# Communication_Ethernet_DP.net
KiCad netlist of a schematic drawn in Altium Designer
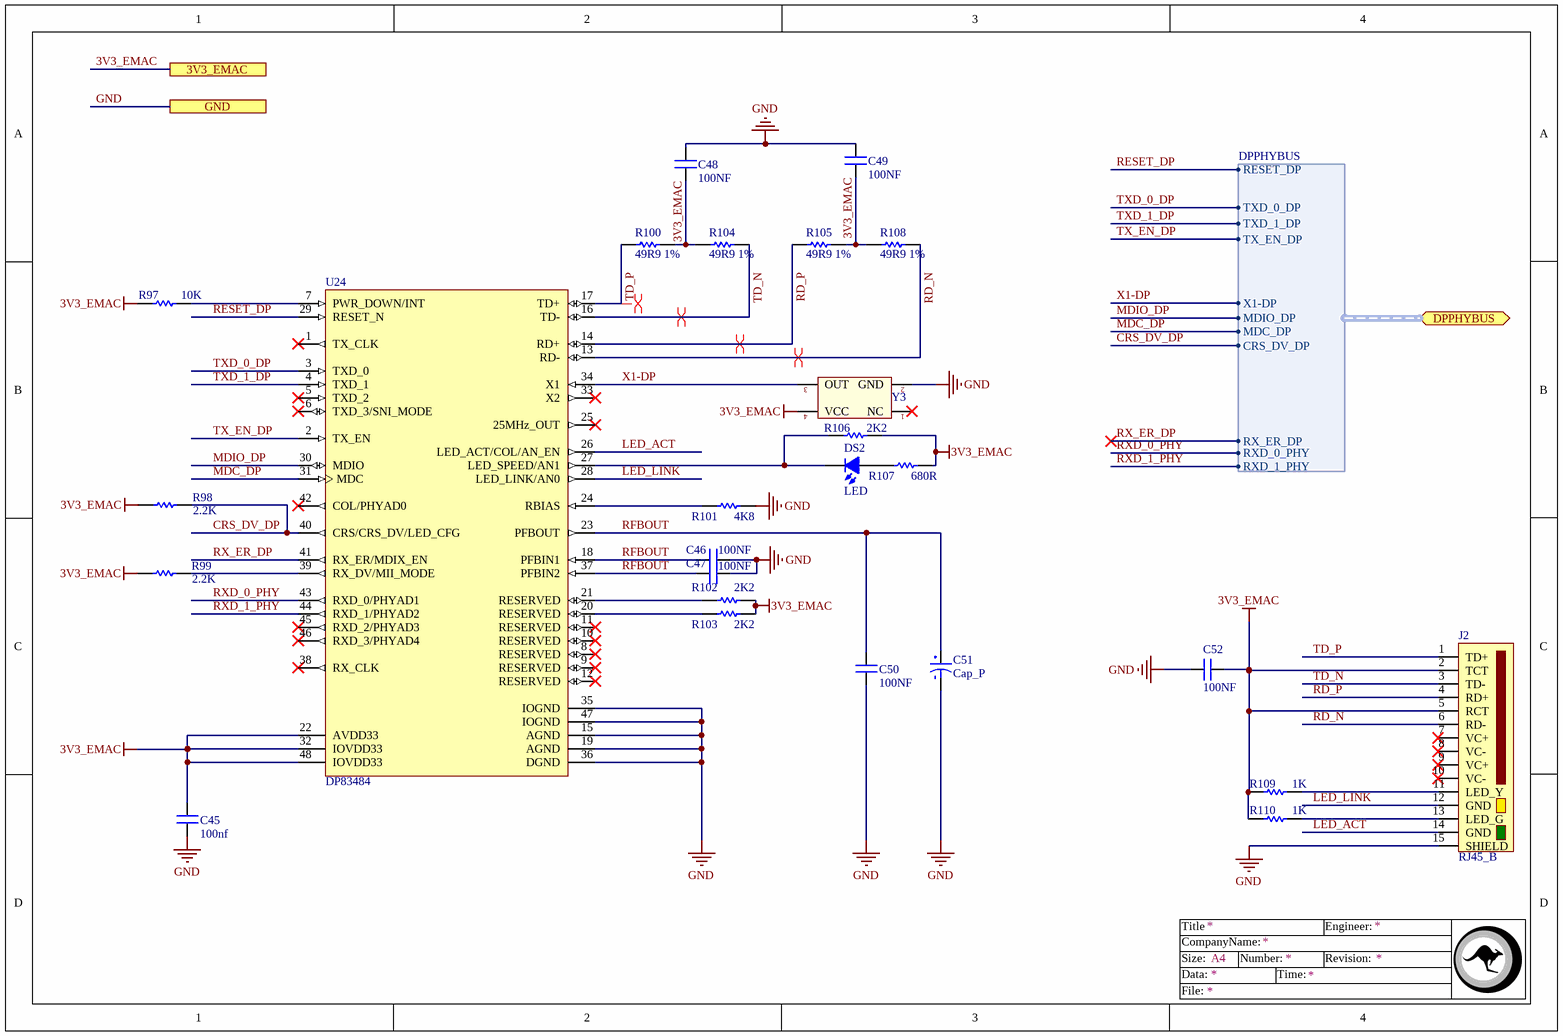
[diagram p0: Communication Ethernet DP.SchDoc]

(export (version "E")
  (design (tool "Eeschema 10.0.6"))
  (components
    (comp (ref "C45")
      (value "100nf")
      (footprint "Cap0805")
      (description "Surface mount Capacitor")
      (libsource (lib "PMLIB2020") (part "Cap"))
    )
    (comp (ref "C46")
      (value "100NF")
      (footprint "Cap0805")
      (description "Surface mount Capacitor")
      (libsource (lib "PMLIB2020") (part "Cap"))
    )
    (comp (ref "C47")
      (value "100NF")
      (footprint "Cap0805")
      (description "Surface mount Capacitor")
      (libsource (lib "PMLIB2020") (part "Cap"))
    )
    (comp (ref "C48")
      (value "100NF")
      (footprint "Cap0805")
      (description "Surface mount Capacitor")
      (libsource (lib "PMLIB2020") (part "Cap"))
    )
    (comp (ref "C49")
      (value "100NF")
      (footprint "Cap0805")
      (description "Surface mount Capacitor")
      (libsource (lib "PMLIB2020") (part "Cap"))
    )
    (comp (ref "C50")
      (value "100NF")
      (footprint "Cap0805")
      (description "Surface mount Capacitor")
      (libsource (lib "PMLIB2020") (part "Cap"))
    )
    (comp (ref "C51")
      (value "Cap_P")
      (footprint "Cap_4mm")
      (description "Polarity")
      (libsource (lib "PMLIB2020") (part "Cap_P"))
    )
    (comp (ref "C52")
      (value "100NF")
      (footprint "Cap0805")
      (description "Surface mount Capacitor")
      (libsource (lib "PMLIB2020") (part "Cap"))
    )
    (comp (ref "DS2") (value "LED") (footprint "Led0805") (libsource (lib "PMLIB2020") (part "LED")))
    (comp (ref "J2")
      (value "RJ45_B")
      (footprint "RJ45_B")
      (description "Ethernet Connector")
      (libsource (lib "PMLIB2020") (part "RJ45_B"))
    )
    (comp (ref "R97")
      (value "10K")
      (footprint "R0805")
      (description "Resistor")
      (libsource (lib "PMLIB2020") (part "Resistor"))
    )
    (comp (ref "R98")
      (value "2.2K")
      (footprint "R0805")
      (description "Resistor")
      (libsource (lib "PMLIB2020") (part "Resistor"))
    )
    (comp (ref "R99")
      (value "2.2K")
      (footprint "R0805")
      (description "Resistor")
      (libsource (lib "PMLIB2020") (part "Resistor"))
    )
    (comp (ref "R100")
      (value "49R9 1%")
      (footprint "R0805")
      (description "Resistor")
      (libsource (lib "PMLIB2020") (part "Resistor"))
    )
    (comp (ref "R101")
      (value "4K8")
      (footprint "R0805")
      (description "Resistor")
      (libsource (lib "PMLIB2020") (part "Resistor"))
    )
    (comp (ref "R102")
      (value "2K2")
      (footprint "R0805")
      (description "Resistor")
      (libsource (lib "PMLIB2020") (part "Resistor"))
    )
    (comp (ref "R103")
      (value "2K2")
      (footprint "R0805")
      (description "Resistor")
      (libsource (lib "PMLIB2020") (part "Resistor"))
    )
    (comp (ref "R104")
      (value "49R9 1%")
      (footprint "R0805")
      (description "Resistor")
      (libsource (lib "PMLIB2020") (part "Resistor"))
    )
    (comp (ref "R105")
      (value "49R9 1%")
      (footprint "R0805")
      (description "Resistor")
      (libsource (lib "PMLIB2020") (part "Resistor"))
    )
    (comp (ref "R106")
      (value "2K2")
      (footprint "R0805")
      (description "Resistor")
      (libsource (lib "PMLIB2020") (part "Resistor"))
    )
    (comp (ref "R107")
      (value "680R")
      (footprint "R0805")
      (description "Resistor")
      (libsource (lib "PMLIB2020") (part "Resistor"))
    )
    (comp (ref "R108")
      (value "49R9 1%")
      (footprint "R0805")
      (description "Resistor")
      (libsource (lib "PMLIB2020") (part "Resistor"))
    )
    (comp (ref "R109")
      (value "1K")
      (footprint "R0805")
      (description "Resistor")
      (libsource (lib "PMLIB2020") (part "Resistor"))
    )
    (comp (ref "R110")
      (value "1K")
      (footprint "R0805")
      (description "Resistor")
      (libsource (lib "PMLIB2020") (part "Resistor"))
    )
    (comp (ref "U24")
      (value "DP83484")
      (footprint "DP83484")
      (description "Ethernet PHY")
      (libsource (lib "PMLIB2020") (part "DP83484"))
    )
    (comp (ref "Y3")
      (value "Oscillator")
      (footprint "Crystall 50Mhz")
      (libsource (lib "PMLIB2020") (part "Oscillator"))
    )
  )
  (nets
    (net (code "2") (name "/CRS_DV_DP") (class "Default")
      (node (ref "R98") (pin "1") (pinfunction "1_1") (pintype "passive"))
      (node (ref "U24") (pin "40") (pinfunction "CRS/CRS_DV/LED_CFG_40") (pintype "output"))
    )
    (net (code "3") (name "/LED_ACT") (class "Default")
      (node (ref "J2") (pin "14") (pinfunction "GND_14") (pintype "passive"))
      (node (ref "U24") (pin "26") (pinfunction "LED_ACT/COL/AN_EN_26") (pintype "output"))
    )
    (net (code "4") (name "/LED_LINK") (class "Default")
      (node (ref "J2") (pin "12") (pinfunction "GND_12") (pintype "passive"))
      (node (ref "U24") (pin "28") (pinfunction "LED_LINK/AN0_28") (pintype "output"))
    )
    (net (code "5") (name "/MDC_DP") (class "Default")
      (node (ref "U24") (pin "31") (pinfunction "MDC_31") (pintype "input"))
    )
    (net (code "6") (name "/MDIO_DP") (class "Default")
      (node (ref "U24") (pin "30") (pinfunction "MDIO_30") (pintype "bidirectional"))
    )
    (net (code "7") (name "/RD_N") (class "Default")
      (node (ref "J2") (pin "6") (pinfunction "RD-_6") (pintype "passive"))
      (node (ref "R108") (pin "2") (pinfunction "2_2") (pintype "passive"))
      (node (ref "U24") (pin "13") (pinfunction "RD-_13") (pintype "bidirectional"))
    )
    (net (code "8") (name "/RD_P") (class "Default")
      (node (ref "J2") (pin "4") (pinfunction "RD+_4") (pintype "passive"))
      (node (ref "R105") (pin "1") (pinfunction "1_1") (pintype "passive"))
      (node (ref "U24") (pin "14") (pinfunction "RD+_14") (pintype "bidirectional"))
    )
    (net (code "9") (name "/RESET_DP") (class "Default")
      (node (ref "U24") (pin "29") (pinfunction "RESET_N_29") (pintype "input"))
    )
    (net (code "10") (name "/RFBOUT") (class "Default")
      (node (ref "C46") (pin "1") (pinfunction "1_1") (pintype "passive"))
      (node (ref "C47") (pin "1") (pinfunction "1_1") (pintype "passive"))
      (node (ref "C50") (pin "2") (pinfunction "2_2") (pintype "passive"))
      (node (ref "C51") (pin "2") (pinfunction "2_2") (pintype "passive"))
      (node (ref "U24") (pin "18") (pinfunction "PFBIN1_18") (pintype "input"))
      (node (ref "U24") (pin "23") (pinfunction "PFBOUT_23") (pintype "output"))
      (node (ref "U24") (pin "37") (pinfunction "PFBIN2_37") (pintype "input"))
    )
    (net (code "11") (name "/RXD_0_PHY") (class "Default")
      (node (ref "U24") (pin "43") (pinfunction "RXD_0/PHYAD1_43") (pintype "output"))
    )
    (net (code "12") (name "/RXD_1_PHY") (class "Default")
      (node (ref "U24") (pin "44") (pinfunction "RXD_1/PHYAD2_44") (pintype "output"))
    )
    (net (code "13") (name "/RX_ER_DP") (class "Default")
      (node (ref "U24") (pin "41") (pinfunction "RX_ER/MDIX_EN_41") (pintype "output"))
    )
    (net (code "14") (name "/TD_N") (class "Default")
      (node (ref "J2") (pin "3") (pinfunction "TD-_3") (pintype "passive"))
      (node (ref "R104") (pin "2") (pinfunction "2_2") (pintype "passive"))
      (node (ref "U24") (pin "16") (pinfunction "TD-_16") (pintype "bidirectional"))
    )
    (net (code "15") (name "/TD_P") (class "Default")
      (node (ref "J2") (pin "1") (pinfunction "TD+_1") (pintype "passive"))
      (node (ref "R100") (pin "1") (pinfunction "1_1") (pintype "passive"))
      (node (ref "U24") (pin "17") (pinfunction "TD+_17") (pintype "bidirectional"))
    )
    (net (code "16") (name "/TXD_0_DP") (class "Default")
      (node (ref "U24") (pin "3") (pinfunction "TXD_0_3") (pintype "input"))
    )
    (net (code "17") (name "/TXD_1_DP") (class "Default")
      (node (ref "U24") (pin "4") (pinfunction "TXD_1_4") (pintype "input"))
    )
    (net (code "18") (name "/TX_EN_DP") (class "Default")
      (node (ref "U24") (pin "2") (pinfunction "TX_EN_2") (pintype "input"))
    )
    (net (code "19") (name "/X1-DP") (class "Default")
      (node (ref "U24") (pin "34") (pinfunction "X1_34") (pintype "input"))
      (node (ref "Y3") (pin "3") (pinfunction "OUT_3") (pintype "passive"))
    )
    (net (code "21") (name "3V3_EMAC") (class "Default")
      (node (ref "C45") (pin "2") (pinfunction "2_2") (pintype "passive"))
      (node (ref "C48") (pin "1") (pinfunction "1_1") (pintype "passive"))
      (node (ref "C49") (pin "1") (pinfunction "1_1") (pintype "passive"))
      (node (ref "C52") (pin "1") (pinfunction "1_1") (pintype "passive"))
      (node (ref "J2") (pin "2") (pinfunction "TCT_2") (pintype "passive"))
      (node (ref "J2") (pin "5") (pinfunction "RCT_5") (pintype "passive"))
      (node (ref "R100") (pin "2") (pinfunction "2_2") (pintype "passive"))
      (node (ref "R102") (pin "1") (pinfunction "1_1") (pintype "passive"))
      (node (ref "R103") (pin "1") (pinfunction "1_1") (pintype "passive"))
      (node (ref "R104") (pin "1") (pinfunction "1_1") (pintype "passive"))
      (node (ref "R105") (pin "2") (pinfunction "2_2") (pintype "passive"))
      (node (ref "R106") (pin "1") (pinfunction "1_1") (pintype "passive"))
      (node (ref "R107") (pin "1") (pinfunction "1_1") (pintype "passive"))
      (node (ref "R108") (pin "1") (pinfunction "1_1") (pintype "passive"))
      (node (ref "R109") (pin "1") (pinfunction "1_1") (pintype "passive"))
      (node (ref "R110") (pin "1") (pinfunction "1_1") (pintype "passive"))
      (node (ref "R97") (pin "2") (pinfunction "2_2") (pintype "passive"))
      (node (ref "R98") (pin "2") (pinfunction "2_2") (pintype "passive"))
      (node (ref "R99") (pin "2") (pinfunction "2_2") (pintype "passive"))
      (node (ref "U24") (pin "22") (pinfunction "AVDD33_22") (pintype "power_in"))
      (node (ref "U24") (pin "32") (pinfunction "IOVDD33_32") (pintype "power_in"))
      (node (ref "U24") (pin "48") (pinfunction "IOVDD33_48") (pintype "power_in"))
      (node (ref "Y3") (pin "4") (pinfunction "VCC_4") (pintype "passive"))
    )
    (net (code "22") (name "GND") (class "Default")
      (node (ref "C45") (pin "1") (pinfunction "1_1") (pintype "passive"))
      (node (ref "C46") (pin "2") (pinfunction "2_2") (pintype "passive"))
      (node (ref "C47") (pin "2") (pinfunction "2_2") (pintype "passive"))
      (node (ref "C48") (pin "2") (pinfunction "2_2") (pintype "passive"))
      (node (ref "C49") (pin "2") (pinfunction "2_2") (pintype "passive"))
      (node (ref "C50") (pin "1") (pinfunction "1_1") (pintype "passive"))
      (node (ref "C51") (pin "1") (pinfunction "1_1") (pintype "passive"))
      (node (ref "C52") (pin "2") (pinfunction "2_2") (pintype "passive"))
      (node (ref "J2") (pin "15") (pinfunction "SHIELD_15") (pintype "passive"))
      (node (ref "R101") (pin "1") (pinfunction "1_1") (pintype "passive"))
      (node (ref "U24") (pin "15") (pinfunction "AGND_15") (pintype "power_in"))
      (node (ref "U24") (pin "19") (pinfunction "AGND_19") (pintype "power_in"))
      (node (ref "U24") (pin "35") (pinfunction "IOGND_35") (pintype "power_in"))
      (node (ref "U24") (pin "36") (pinfunction "DGND_36") (pintype "power_in"))
      (node (ref "U24") (pin "47") (pinfunction "IOGND_47") (pintype "power_in"))
      (node (ref "Y3") (pin "2") (pinfunction "GND_2") (pintype "passive"))
    )
    (net (code "23") (name "Net-(DS2-PadA)") (class "Default")
      (node (ref "DS2") (pin "A") (pinfunction "A_A") (pintype "passive"))
      (node (ref "R107") (pin "2") (pinfunction "2_2") (pintype "passive"))
    )
    (net (code "24") (name "Net-(J2-LED_G)") (class "Default")
      (node (ref "J2") (pin "13") (pinfunction "LED_G_13") (pintype "passive"))
      (node (ref "R110") (pin "2") (pinfunction "2_2") (pintype "passive"))
    )
    (net (code "25") (name "Net-(J2-LED_Y)") (class "Default")
      (node (ref "J2") (pin "11") (pinfunction "LED_Y_11") (pintype "passive"))
      (node (ref "R109") (pin "2") (pinfunction "2_2") (pintype "passive"))
    )
    (net (code "26") (name "Net-(R102-Pad2)") (class "Default")
      (node (ref "R102") (pin "2") (pinfunction "2_2") (pintype "passive"))
      (node (ref "U24") (pin "21") (pinfunction "RESERVED_21") (pintype "bidirectional"))
    )
    (net (code "27") (name "Net-(R103-Pad2)") (class "Default")
      (node (ref "R103") (pin "2") (pinfunction "2_2") (pintype "passive"))
      (node (ref "U24") (pin "20") (pinfunction "RESERVED_20") (pintype "bidirectional"))
    )
    (net (code "28") (name "Net-(U24-LED_SPEED{slash}AN1)") (class "Default")
      (node (ref "DS2") (pin "K") (pinfunction "K_K") (pintype "passive"))
      (node (ref "R106") (pin "2") (pinfunction "2_2") (pintype "passive"))
      (node (ref "U24") (pin "27") (pinfunction "LED_SPEED/AN1_27") (pintype "output"))
    )
    (net (code "29") (name "Net-(U24-PWR_DOWN{slash}INT)") (class "Default")
      (node (ref "R97") (pin "1") (pinfunction "1_1") (pintype "passive"))
      (node (ref "U24") (pin "7") (pinfunction "PWR_DOWN/INT_7") (pintype "input"))
    )
    (net (code "30") (name "Net-(U24-RBIAS)") (class "Default")
      (node (ref "R101") (pin "2") (pinfunction "2_2") (pintype "passive"))
      (node (ref "U24") (pin "24") (pinfunction "RBIAS_24") (pintype "input"))
    )
    (net (code "31") (name "Net-(U24-RX_DV{slash}MII_MODE)") (class "Default")
      (node (ref "R99") (pin "1") (pinfunction "1_1") (pintype "passive"))
      (node (ref "U24") (pin "39") (pinfunction "RX_DV/MII_MODE_39") (pintype "output"))
    )
    (net (code "32") (name "unconnected-(J2-VC+-Pad7)") (class "Default")
      (node (ref "J2") (pin "7") (pinfunction "VC+_7") (pintype "passive+no_connect"))
    )
    (net (code "33") (name "unconnected-(J2-VC+-Pad9)") (class "Default")
      (node (ref "J2") (pin "9") (pinfunction "VC+_9") (pintype "passive+no_connect"))
    )
    (net (code "34") (name "unconnected-(J2-VC--Pad8)") (class "Default")
      (node (ref "J2") (pin "8") (pinfunction "VC-_8") (pintype "passive+no_connect"))
    )
    (net (code "35") (name "unconnected-(J2-VC--Pad10)") (class "Default")
      (node (ref "J2") (pin "10") (pinfunction "VC-_10") (pintype "passive+no_connect"))
    )
    (net (code "36") (name "unconnected-(U24-25MHz_OUT-Pad25)") (class "Default")
      (node (ref "U24") (pin "25") (pinfunction "25MHz_OUT_25") (pintype "output+no_connect"))
    )
    (net (code "37") (name "unconnected-(U24-COL{slash}PHYAD0-Pad42)") (class "Default")
      (node (ref "U24") (pin "42") (pinfunction "COL/PHYAD0_42") (pintype "output+no_connect"))
    )
    (net (code "38") (name "unconnected-(U24-RESERVED-Pad8)") (class "Default")
      (node (ref "U24") (pin "8") (pinfunction "RESERVED_8") (pintype "bidirectional+no_connect"))
    )
    (net (code "39") (name "unconnected-(U24-RESERVED-Pad9)") (class "Default")
      (node (ref "U24") (pin "9") (pinfunction "RESERVED_9") (pintype "bidirectional+no_connect"))
    )
    (net (code "40") (name "unconnected-(U24-RESERVED-Pad10)") (class "Default")
      (node (ref "U24") (pin "10") (pinfunction "RESERVED_10") (pintype "bidirectional+no_connect"))
    )
    (net (code "41") (name "unconnected-(U24-RESERVED-Pad11)") (class "Default")
      (node (ref "U24") (pin "11") (pinfunction "RESERVED_11") (pintype "bidirectional+no_connect"))
    )
    (net (code "42") (name "unconnected-(U24-RESERVED-Pad12)") (class "Default")
      (node (ref "U24") (pin "12") (pinfunction "RESERVED_12") (pintype "bidirectional+no_connect"))
    )
    (net (code "43") (name "unconnected-(U24-RXD_2{slash}PHYAD3-Pad45)") (class "Default")
      (node (ref "U24") (pin "45") (pinfunction "RXD_2/PHYAD3_45") (pintype "output+no_connect"))
    )
    (net (code "44") (name "unconnected-(U24-RXD_3{slash}PHYAD4-Pad46)") (class "Default")
      (node (ref "U24") (pin "46") (pinfunction "RXD_3/PHYAD4_46") (pintype "output+no_connect"))
    )
    (net (code "45") (name "unconnected-(U24-RX_CLK-Pad38)") (class "Default")
      (node (ref "U24") (pin "38") (pinfunction "RX_CLK_38") (pintype "output+no_connect"))
    )
    (net (code "46") (name "unconnected-(U24-TXD_2-Pad5)") (class "Default")
      (node (ref "U24") (pin "5") (pinfunction "TXD_2_5") (pintype "input+no_connect"))
    )
    (net (code "47") (name "unconnected-(U24-TXD_3{slash}SNI_MODE-Pad6)") (class "Default")
      (node (ref "U24") (pin "6") (pinfunction "TXD_3/SNI_MODE_6") (pintype "bidirectional+no_connect"))
    )
    (net (code "48") (name "unconnected-(U24-TX_CLK-Pad1)") (class "Default")
      (node (ref "U24") (pin "1") (pinfunction "TX_CLK_1") (pintype "output+no_connect"))
    )
    (net (code "49") (name "unconnected-(U24-X2-Pad33)") (class "Default")
      (node (ref "U24") (pin "33") (pinfunction "X2_33") (pintype "output+no_connect"))
    )
    (net (code "50") (name "unconnected-(Y3-NC-Pad1)") (class "Default")
      (node (ref "Y3") (pin "1") (pinfunction "NC_1") (pintype "passive+no_connect"))
    )
  )
)
